# pca10156_sheet7_connectors.net
KiCad netlist of a schematic drawn in Altium Designer
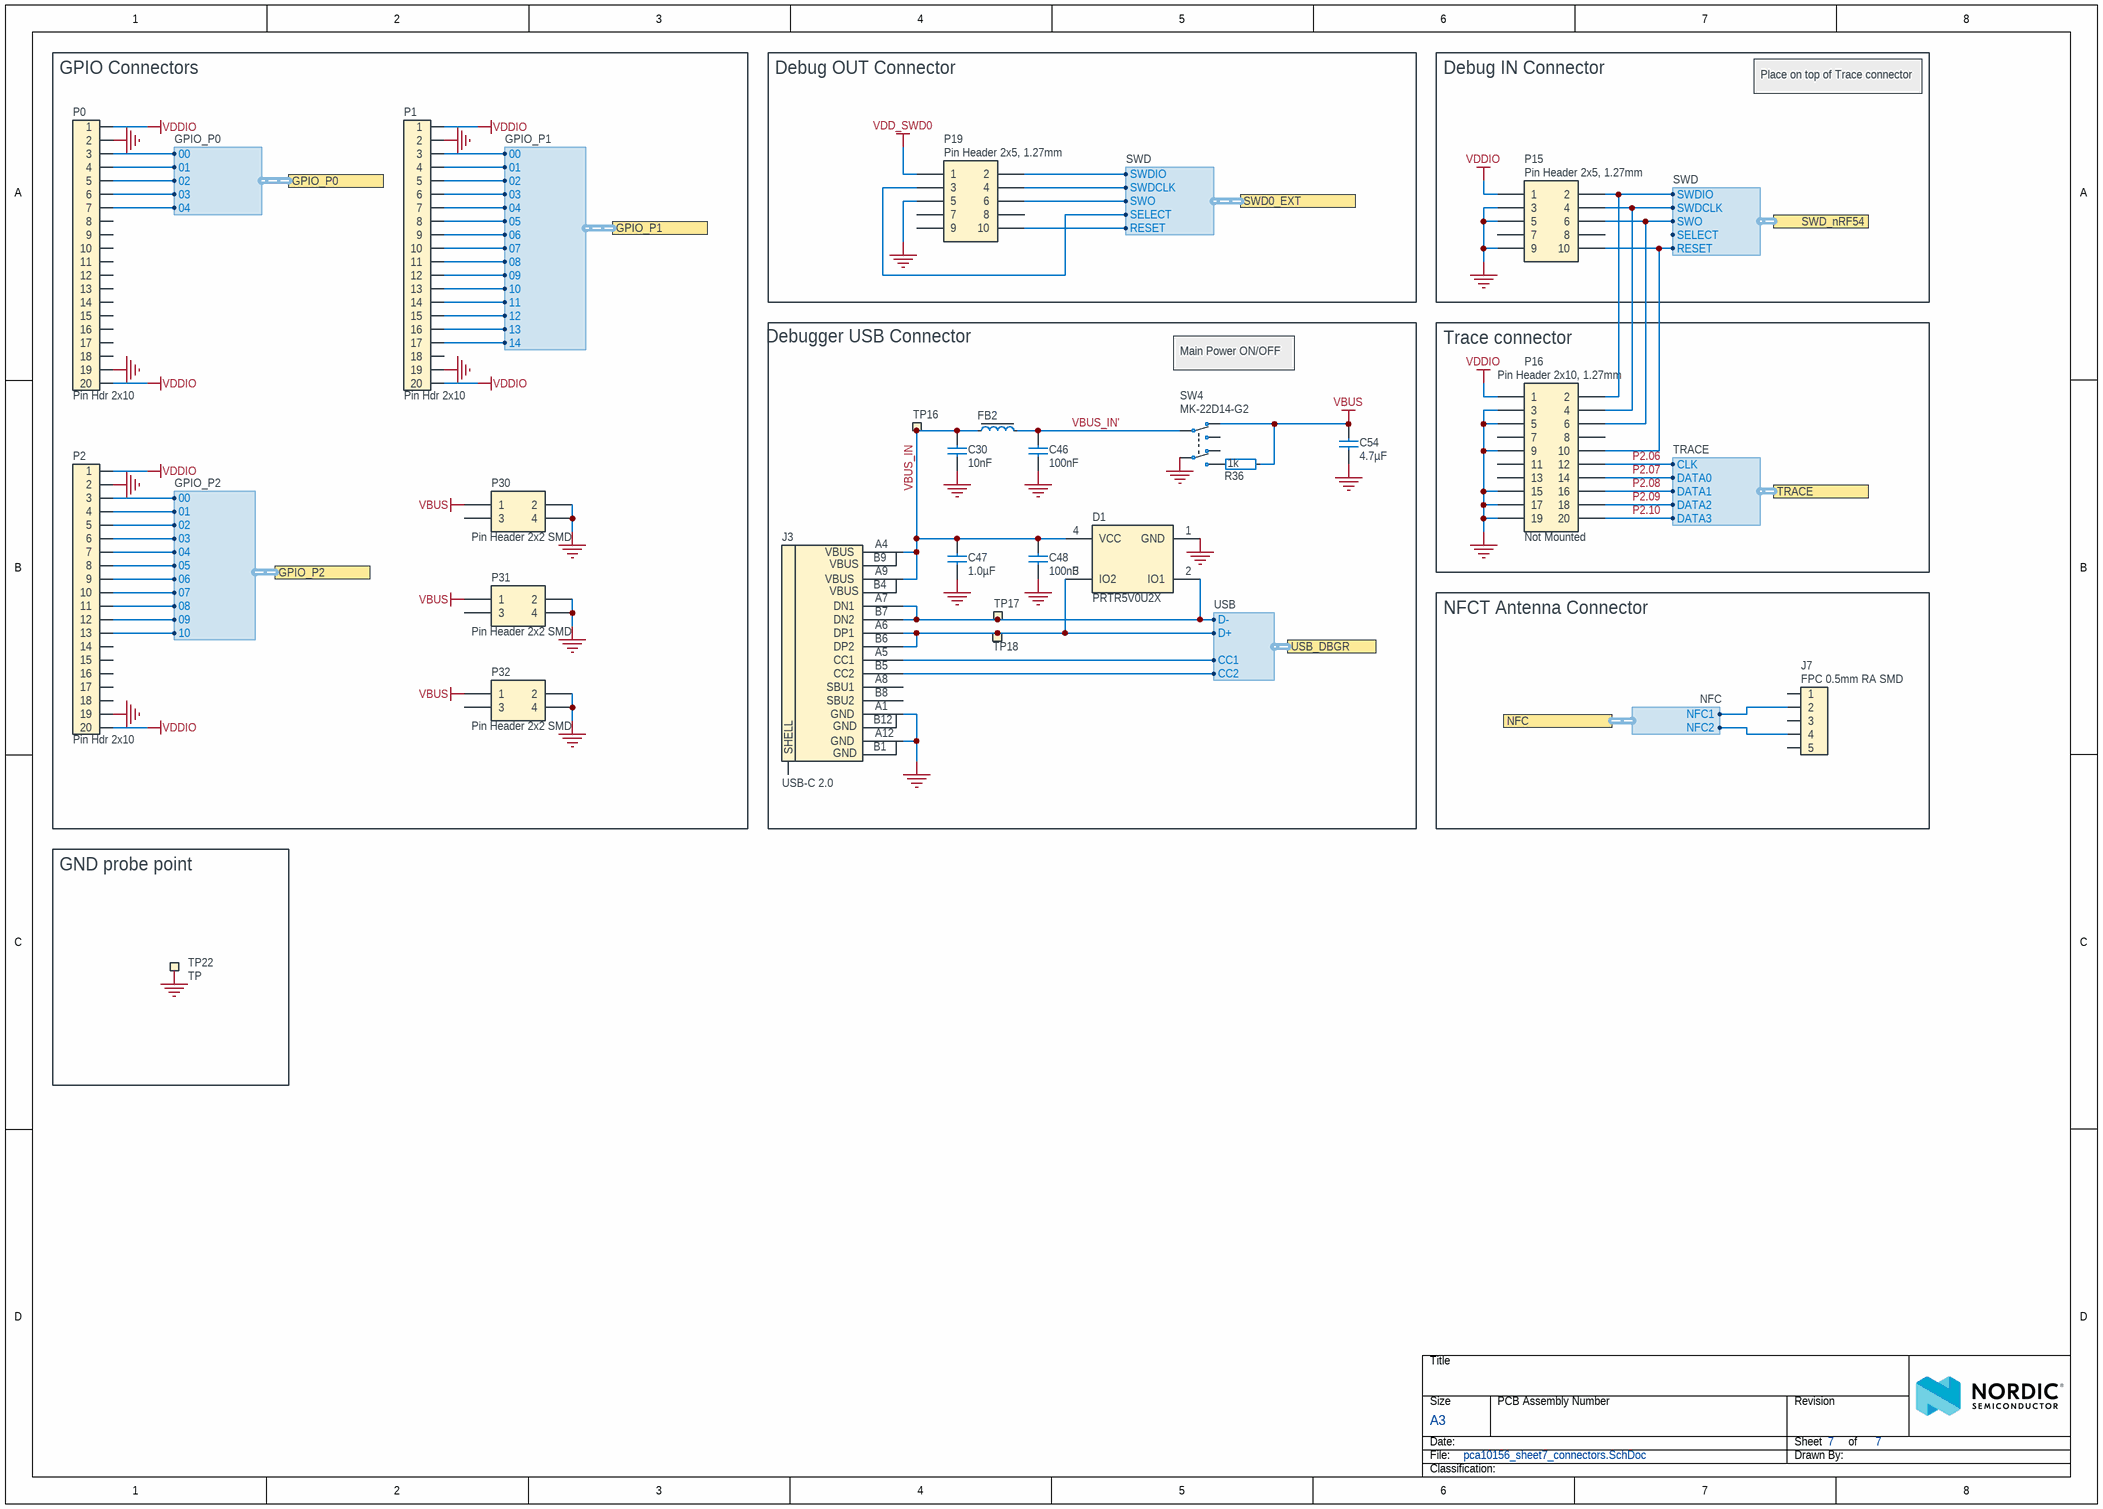
[diagram p0: pca10156_sheet7_connectors.SchDoc]

(export (version "E")
  (design (tool "Eeschema 10.0.6"))
  (components
    (comp (ref "C30")
      (value "10nF")
      (footprint "CAPC0603X03L_C")
      (description "Capacitor, X7R, ±10%")
      (fields
        (field (name "PART NUMBER") "C0201-10n")
        (field (name "MANUFACTURER") "N.A.")
        (field (name "AUTHOR") "rsk")
      )
      (libsource (lib "AltiumLib") (part "CAP"))
    )
    (comp (ref "C46")
      (value "100nF")
      (footprint "CAPC0603X03L_C")
      (description "Capacitor, X5R, ±10%")
      (fields
        (field (name "PART NUMBER") "C0201-100n")
        (field (name "MANUFACTURER") "N.A.")
        (field (name "AUTHOR") "rsk")
      )
      (libsource (lib "AltiumLib") (part "CAP"))
    )
    (comp (ref "C47")
      (value "1.0µF")
      (footprint "CAPC1005X04L")
      (description "Capacitor, Ceramic, X5R, ±10%, 16V")
      (fields
        (field (name "PART NUMBER") "C0402-1µ0-16V-X5R")
        (field (name "MANUFACTURER") "Murata")
        (field (name "AUTHOR") "rsk")
      )
      (libsource (lib "AltiumLib") (part "CAP"))
    )
    (comp (ref "C48")
      (value "100nF")
      (footprint "CAPC0603X03L_C")
      (description "Capacitor, X5R, ±10%")
      (fields
        (field (name "PART NUMBER") "C0201-100n")
        (field (name "MANUFACTURER") "N.A.")
        (field (name "AUTHOR") "rsk")
      )
      (libsource (lib "AltiumLib") (part "CAP"))
    )
    (comp (ref "C54")
      (value "4.7µF")
      (footprint "CAPC1608X06L")
      (description "Capacitor, X7S, ±10%, 10V")
      (fields
        (field (name "PART NUMBER") "C0603-4µ7-10V-X7S")
        (field (name "MANUFACTURER") "N.A.")
        (field (name "AUTHOR") "rsk")
      )
      (libsource (lib "AltiumLib") (part "CAP"))
    )
    (comp (ref "D1")
      (value "PRTR5V0U2X")
      (footprint "SOT190P230X110-4L")
      (description "Ultra low capacitance double rail-to-rail ESD protection diode")
      (fields (field (name "MANUFACTURER") "NXP Semiconductors") (field (name "AUTHOR") "rsk"))
      (libsource (lib "AltiumLib") (part "PRTR5V0U2X"))
    )
    (comp (ref "FB2")
      (value "120R/0.55A")
      (footprint "INDC1005X04L")
      (description "Ferrite Bead, 120 Ohm @ 100MHz, 500mA, 250 mOhm Max")
      (fields
        (field (name "PART NUMBER") "FB0402-120R@100M-500mA")
        (field (name "MANUFACTURER") "Murata")
        (field (name "AUTHOR") "rsk")
      )
      (libsource (lib "AltiumLib") (part "IND_F"))
    )
    (comp (ref "J3")
      (value "USB-C 2.0")
      (footprint "SD-80259-001")
      (description "USB-C Receptacle, 16 Pin, USB 2.0")
      (fields
        (field (name "PART NUMBER") "SD-80259-1021")
        (field (name "MANUFACTURER") "Bellweather Electronic Corp.")
        (field (name "AUTHOR") "getr")
      )
      (libsource (lib "AltiumLib") (part "USB4110"))
    )
    (comp (ref "J7")
      (value "FPC 0.5mm RA SMD")
      (footprint "FPC_05P-0.5mm-RA-SMD")
      (description "0.5mm FPC, 5P,Right Angle SMT,Double Contact,H=1.2mm,White, Tin plated")
      (fields
        (field (name "PART NUMBER") "FPC_05P-0.5mm-RA-SMD")
        (field (name "MANUFACTURER") "WCON")
        (field (name "AUTHOR") "rsk")
      )
      (libsource (lib "AltiumLib") (part "CONN-5"))
    )
    (comp (ref "P0")
      (value "Pin Hdr 2x10")
      (footprint "HDR_2x10-SMD")
      (description "Pin Header 2x10, 2.54mm (100mil) SMD")
      (fields
        (field (name "PART NUMBER") "Pin Header 2x10 SMD, 2.54mm")
        (field (name "MANUFACTURER") "WCON")
        (field (name "AUTHOR") "stl1")
      )
      (libsource (lib "AltiumLib") (part "CONN-20"))
    )
    (comp (ref "P1")
      (value "Pin Hdr 2x10")
      (footprint "HDR_2x10-SMD")
      (description "Pin Header 2x10, 2.54mm (100mil) SMD")
      (fields
        (field (name "PART NUMBER") "Pin Header 2x10 SMD, 2.54mm")
        (field (name "MANUFACTURER") "WCON")
        (field (name "AUTHOR") "stl1")
      )
      (libsource (lib "AltiumLib") (part "CONN-20"))
    )
    (comp (ref "P2")
      (value "Pin Hdr 2x10")
      (footprint "HDR_2x10-SMD")
      (description "Pin Header 2x10, 2.54mm (100mil) SMD")
      (fields
        (field (name "PART NUMBER") "Pin Header 2x10 SMD, 2.54mm")
        (field (name "MANUFACTURER") "WCON")
        (field (name "AUTHOR") "stl1")
      )
      (libsource (lib "AltiumLib") (part "CONN-20"))
    )
    (comp (ref "P15")
      (value "Pin Header 2x5, 1.27mm")
      (footprint "HDR_2x5-SMD-1.27mm-K")
      (description "Pin Header 2x5, 1.27mm (50mil), SMD, Keying Shroud")
      (fields
        (field (name "PART NUMBER") "Pin Header 2x5 SMD, 1.27mm, KS")
        (field (name "MANUFACTURER") "WCON")
        (field (name "AUTHOR") "rsk")
      )
      (libsource (lib "AltiumLib") (part "CONN-2x5"))
    )
    (comp (ref "P16")
      (value "Pin Header 2x10, 1.27mm")
      (footprint "HDR_2x10-SMD-1.27mm-NC")
      (description "Pin Header 2x10, 1.27mm (50mil), SMD, Keying Shroud")
      (fields
        (field (name "PART NUMBER") "Pin Header 2x10 SMD, 1.27mm, KS, N.C.")
        (field (name "MANUFACTURER") "WCON")
        (field (name "ASSEMBLY") "Not Mounted")
        (field (name "AUTHOR") "rsk")
      )
      (libsource (lib "AltiumLib") (part "CONN-2x10"))
    )
    (comp (ref "P19")
      (value "Pin Header 2x5, 1.27mm")
      (footprint "HDR_2x5-SMD-1.27mm-K")
      (description "Pin Header 2x5, 1.27mm (50mil), SMD, Keying Shroud")
      (fields
        (field (name "PART NUMBER") "Pin Header 2x5 SMD, 1.27mm, KS")
        (field (name "MANUFACTURER") "WCON")
        (field (name "AUTHOR") "rsk")
      )
      (libsource (lib "AltiumLib") (part "CONN-2x5"))
    )
    (comp (ref "P30")
      (value "Pin Header 2x2 SMD")
      (footprint "HDR_2x2-SMD")
      (description "Pin Header 2x2, SMD, 2.54mm (100mil)")
      (fields
        (field (name "MANUFACTURER") "WCON")
        (field (name "MANUFACTURER PART NUMBER") "1125-1202S0M116CR03")
        (field (name "AUTHOR") "stl1")
      )
      (libsource (lib "AltiumLib") (part "CONN-2x2"))
    )
    (comp (ref "P31")
      (value "Pin Header 2x2 SMD")
      (footprint "HDR_2x2-SMD")
      (description "Pin Header 2x2, SMD, 2.54mm (100mil)")
      (fields
        (field (name "MANUFACTURER") "WCON")
        (field (name "MANUFACTURER PART NUMBER") "1125-1202S0M116CR03")
        (field (name "AUTHOR") "stl1")
      )
      (libsource (lib "AltiumLib") (part "CONN-2x2"))
    )
    (comp (ref "P32")
      (value "Pin Header 2x2 SMD")
      (footprint "HDR_2x2-SMD")
      (description "Pin Header 2x2, SMD, 2.54mm (100mil)")
      (fields
        (field (name "MANUFACTURER") "WCON")
        (field (name "MANUFACTURER PART NUMBER") "1125-1202S0M116CR03")
        (field (name "AUTHOR") "stl1")
      )
      (libsource (lib "AltiumLib") (part "CONN-2x2"))
    )
    (comp (ref "R36")
      (value "1k")
      (footprint "RESC0603X03L_C")
      (description "Resistor, ±1%, 0.05W")
      (fields
        (field (name "PART NUMBER") "R0201-1k0")
        (field (name "MANUFACTURER") "N.A.")
        (field (name "AUTHOR") "rsk")
      )
      (libsource (lib "AltiumLib") (part "RES"))
    )
    (comp (ref "SW4")
      (value "MK-22D14-G2")
      (footprint "MK-22D14-G2")
      (description "Slide Switch DPDT")
      (fields (field (name "MANUFACTURER") "HUA-JIE CORP.") (field (name "AUTHOR") "rsk"))
      (libsource (lib "AltiumLib") (part "SW-DPDT"))
    )
    (comp (ref "TP16")
      (value "Ø1.5mm,SMD")
      (footprint "TP_SMD_D1.5mm")
      (description "1.5mm circular SMD testpad")
      (fields
        (field (name "PART NUMBER") "TP_SMD_Ø1.5MM")
        (field (name "MANUFACTURER") "Nordic Semiconductor")
        (field (name "AUTHOR") "rsk")
      )
      (libsource (lib "") (part "TESTPAD_1"))
    )
    (comp (ref "TP17")
      (value "Ø1.5mm,SMD")
      (footprint "TP_SMD_D1.5mm")
      (description "1.5mm circular SMD testpad")
      (fields
        (field (name "PART NUMBER") "TP_SMD_Ø1.5MM")
        (field (name "MANUFACTURER") "Nordic Semiconductor")
        (field (name "AUTHOR") "rsk")
      )
      (libsource (lib "") (part "TESTPAD_1"))
    )
    (comp (ref "TP18")
      (value "Ø1.5mm,SMD")
      (footprint "TP_SMD_D1.5mm")
      (description "1.5mm circular SMD testpad")
      (fields
        (field (name "PART NUMBER") "TP_SMD_Ø1.5MM")
        (field (name "MANUFACTURER") "Nordic Semiconductor")
        (field (name "AUTHOR") "rsk")
      )
      (libsource (lib "AltiumLib") (part "TESTPAD"))
    )
    (comp (ref "TP22")
      (value "TP")
      (footprint "S1751")
      (description "PC TEST POINT TIN SMD L")
      (fields
        (field (name "PART NUMBER") "TP - S1751-46R")
        (field (name "MANUFACTURER") "Harwin")
        (field (name "AUTHOR") "rsk")
      )
      (libsource (lib "AltiumLib") (part "TESTPOINT_BOM"))
    )
  )
  (nets
    (net (code "8") (name "/11") (class "Default")
      (node (ref "P1") (pin "14") (pinfunction "14_14") (pintype "passive"))
    )
    (net (code "9") (name "/12") (class "Default")
      (node (ref "P1") (pin "15") (pinfunction "15_15") (pintype "passive"))
    )
    (net (code "10") (name "/13") (class "Default")
      (node (ref "P1") (pin "16") (pinfunction "16_16") (pintype "passive"))
    )
    (net (code "11") (name "/14") (class "Default")
      (node (ref "P1") (pin "17") (pinfunction "17_17") (pintype "passive"))
    )
    (net (code "12") (name "/CC1") (class "Default")
      (node (ref "J3") (pin "A5") (pinfunction "CC1_A5") (pintype "passive"))
    )
    (net (code "13") (name "/CC2") (class "Default")
      (node (ref "J3") (pin "B5") (pinfunction "CC2_B5") (pintype "passive"))
    )
    (net (code "14") (name "/D+") (class "Default")
      (node (ref "D1") (pin "3") (pinfunction "IO2_3") (pintype "passive"))
      (node (ref "J3") (pin "A6") (pinfunction "DP1_A6") (pintype "passive"))
      (node (ref "J3") (pin "B6") (pinfunction "DP2_B6") (pintype "passive"))
      (node (ref "TP18") (pin "1") (pinfunction "1_1") (pintype "passive"))
    )
    (net (code "15") (name "/D-") (class "Default")
      (node (ref "D1") (pin "2") (pinfunction "IO1_2") (pintype "passive"))
      (node (ref "J3") (pin "A7") (pinfunction "DN1_A7") (pintype "passive"))
      (node (ref "J3") (pin "B7") (pinfunction "DN2_B7") (pintype "passive"))
      (node (ref "TP17") (pin "1") (pinfunction "1_1") (pintype "passive"))
    )
    (net (code "16") (name "/NFC1") (class "Default")
      (node (ref "J7") (pin "2") (pinfunction "2_2") (pintype "passive"))
    )
    (net (code "17") (name "/NFC2") (class "Default")
      (node (ref "J7") (pin "4") (pinfunction "4_4") (pintype "passive"))
    )
    (net (code "18") (name "/P2.06") (class "Default")
      (node (ref "P16") (pin "12") (pinfunction "12_12") (pintype "passive"))
    )
    (net (code "19") (name "/P2.07") (class "Default")
      (node (ref "P16") (pin "14") (pinfunction "14_14") (pintype "passive"))
    )
    (net (code "20") (name "/P2.08") (class "Default")
      (node (ref "P16") (pin "16") (pinfunction "16_16") (pintype "passive"))
    )
    (net (code "21") (name "/P2.09") (class "Default")
      (node (ref "P16") (pin "18") (pinfunction "18_18") (pintype "passive"))
    )
    (net (code "22") (name "/P2.10") (class "Default")
      (node (ref "P16") (pin "20") (pinfunction "20_20") (pintype "passive"))
    )
    (net (code "23") (name "/VBUS_IN") (class "Default")
      (node (ref "C30") (pin "1") (pinfunction "1_1") (pintype "passive"))
      (node (ref "C47") (pin "2") (pinfunction "2_2") (pintype "passive"))
      (node (ref "C48") (pin "2") (pinfunction "2_2") (pintype "passive"))
      (node (ref "D1") (pin "4") (pinfunction "VCC_4") (pintype "passive"))
      (node (ref "FB2") (pin "1") (pinfunction "1_1") (pintype "passive"))
      (node (ref "J3") (pin "A4") (pinfunction "VBUS_A4") (pintype "power_in"))
      (node (ref "J3") (pin "A9") (pinfunction "VBUS_A9") (pintype "power_in"))
      (node (ref "TP16") (pin "1") (pinfunction "1_1") (pintype "passive"))
    )
    (net (code "24") (name "/VBUS_IN'") (class "Default")
      (node (ref "C46") (pin "2") (pinfunction "2_2") (pintype "passive"))
      (node (ref "FB2") (pin "2") (pinfunction "2_2") (pintype "passive"))
      (node (ref "SW4") (pin "2") (pinfunction "COM-1_2") (pintype "passive"))
    )
    (net (code "32") (name "GND") (class "Default")
      (node (ref "C30") (pin "2") (pinfunction "2_2") (pintype "passive"))
      (node (ref "C46") (pin "1") (pinfunction "1_1") (pintype "passive"))
      (node (ref "C47") (pin "1") (pinfunction "1_1") (pintype "passive"))
      (node (ref "C48") (pin "1") (pinfunction "1_1") (pintype "passive"))
      (node (ref "C54") (pin "2") (pinfunction "2_2") (pintype "passive"))
      (node (ref "D1") (pin "1") (pinfunction "GND_1") (pintype "passive"))
      (node (ref "J3") (pin "A1") (pinfunction "GND_A1") (pintype "power_in"))
      (node (ref "J3") (pin "A12") (pinfunction "GND_A12") (pintype "power_in"))
      (node (ref "P0") (pin "19") (pinfunction "19_19") (pintype "passive"))
      (node (ref "P0") (pin "2") (pinfunction "2_2") (pintype "passive"))
      (node (ref "P1") (pin "19") (pinfunction "19_19") (pintype "passive"))
      (node (ref "P1") (pin "2") (pinfunction "2_2") (pintype "passive"))
      (node (ref "P15") (pin "3") (pinfunction "3_3") (pintype "passive"))
      (node (ref "P15") (pin "5") (pinfunction "5_5") (pintype "passive"))
      (node (ref "P15") (pin "9") (pinfunction "9_9") (pintype "passive"))
      (node (ref "P16") (pin "15") (pinfunction "15_15") (pintype "passive"))
      (node (ref "P16") (pin "17") (pinfunction "17_17") (pintype "passive"))
      (node (ref "P16") (pin "19") (pinfunction "19_19") (pintype "passive"))
      (node (ref "P16") (pin "3") (pinfunction "3_3") (pintype "passive"))
      (node (ref "P16") (pin "5") (pinfunction "5_5") (pintype "passive"))
      (node (ref "P16") (pin "9") (pinfunction "9_9") (pintype "passive"))
      (node (ref "P19") (pin "5") (pinfunction "5_5") (pintype "passive"))
      (node (ref "P2") (pin "19") (pinfunction "19_19") (pintype "passive"))
      (node (ref "P2") (pin "2") (pinfunction "2_2") (pintype "passive"))
      (node (ref "P30") (pin "2") (pinfunction "2_2") (pintype "passive"))
      (node (ref "P30") (pin "4") (pinfunction "4_4") (pintype "passive"))
      (node (ref "P31") (pin "2") (pinfunction "2_2") (pintype "passive"))
      (node (ref "P31") (pin "4") (pinfunction "4_4") (pintype "passive"))
      (node (ref "P32") (pin "2") (pinfunction "2_2") (pintype "passive"))
      (node (ref "P32") (pin "4") (pinfunction "4_4") (pintype "passive"))
      (node (ref "SW4") (pin "5") (pinfunction "COM-2_5") (pintype "passive"))
      (node (ref "TP22") (pin "1") (pinfunction "1_1") (pintype "passive"))
    )
    (net (code "33") (name "Net-(P15-Pad2)") (class "Default")
      (node (ref "P15") (pin "2") (pinfunction "2_2") (pintype "passive"))
      (node (ref "P16") (pin "2") (pinfunction "2_2") (pintype "passive"))
    )
    (net (code "34") (name "Net-(P15-Pad4)") (class "Default")
      (node (ref "P15") (pin "4") (pinfunction "4_4") (pintype "passive"))
      (node (ref "P16") (pin "4") (pinfunction "4_4") (pintype "passive"))
    )
    (net (code "35") (name "Net-(P15-Pad6)") (class "Default")
      (node (ref "P15") (pin "6") (pinfunction "6_6") (pintype "passive"))
      (node (ref "P16") (pin "6") (pinfunction "6_6") (pintype "passive"))
    )
    (net (code "36") (name "Net-(P15-Pad10)") (class "Default")
      (node (ref "P15") (pin "10") (pinfunction "10_10") (pintype "passive"))
      (node (ref "P16") (pin "10") (pinfunction "10_10") (pintype "passive"))
    )
    (net (code "37") (name "Net-(SW4-N.O-2)") (class "Default")
      (node (ref "R36") (pin "1") (pinfunction "1_1") (pintype "passive"))
      (node (ref "SW4") (pin "4") (pinfunction "N.O-2_4") (pintype "passive"))
    )
    (net (code "38") (name "VBUS") (class "Default")
      (node (ref "C54") (pin "1") (pinfunction "1_1") (pintype "passive"))
      (node (ref "P30") (pin "1") (pinfunction "1_1") (pintype "passive"))
      (node (ref "P31") (pin "1") (pinfunction "1_1") (pintype "passive"))
      (node (ref "P32") (pin "1") (pinfunction "1_1") (pintype "passive"))
      (node (ref "R36") (pin "2") (pinfunction "2_2") (pintype "passive"))
      (node (ref "SW4") (pin "3") (pinfunction "N.C-1_3") (pintype "passive"))
    )
    (net (code "39") (name "VDDIO") (class "Default")
      (node (ref "P0") (pin "1") (pinfunction "1_1") (pintype "passive"))
      (node (ref "P0") (pin "20") (pinfunction "20_20") (pintype "passive"))
      (node (ref "P1") (pin "1") (pinfunction "1_1") (pintype "passive"))
      (node (ref "P1") (pin "20") (pinfunction "20_20") (pintype "passive"))
      (node (ref "P15") (pin "1") (pinfunction "1_1") (pintype "passive"))
      (node (ref "P16") (pin "1") (pinfunction "1_1") (pintype "passive"))
      (node (ref "P2") (pin "1") (pinfunction "1_1") (pintype "passive"))
      (node (ref "P2") (pin "20") (pinfunction "20_20") (pintype "passive"))
    )
    (net (code "40") (name "VDD_SWD0") (class "Default")
      (node (ref "P19") (pin "1") (pinfunction "1_1") (pintype "passive"))
    )
    (net (code "41") (name "unconnected-(J3-SBU1-PadA8)") (class "Default")
      (node (ref "J3") (pin "A8") (pinfunction "SBU1_A8") (pintype "passive"))
    )
    (net (code "42") (name "unconnected-(J3-SBU2-PadB8)") (class "Default")
      (node (ref "J3") (pin "B8") (pinfunction "SBU2_B8") (pintype "passive"))
    )
    (net (code "43") (name "unconnected-(J3-SHELL-PadSHLD)") (class "Default")
      (node (ref "J3") (pin "SHLD") (pinfunction "SHELL_SHLD") (pintype "power_in"))
    )
    (net (code "44") (name "unconnected-(J7-Pad1)") (class "Default")
      (node (ref "J7") (pin "1") (pinfunction "1_1") (pintype "passive"))
    )
    (net (code "45") (name "unconnected-(J7-Pad3)") (class "Default")
      (node (ref "J7") (pin "3") (pinfunction "3_3") (pintype "passive"))
    )
    (net (code "46") (name "unconnected-(J7-Pad5)") (class "Default")
      (node (ref "J7") (pin "5") (pinfunction "5_5") (pintype "passive"))
    )
    (net (code "47") (name "unconnected-(P0-Pad3)") (class "Default")
      (node (ref "P0") (pin "3") (pinfunction "3_3") (pintype "passive"))
    )
    (net (code "48") (name "unconnected-(P0-Pad4)") (class "Default")
      (node (ref "P0") (pin "4") (pinfunction "4_4") (pintype "passive"))
    )
    (net (code "49") (name "unconnected-(P0-Pad5)") (class "Default")
      (node (ref "P0") (pin "5") (pinfunction "5_5") (pintype "passive"))
    )
    (net (code "50") (name "unconnected-(P0-Pad6)") (class "Default")
      (node (ref "P0") (pin "6") (pinfunction "6_6") (pintype "passive"))
    )
    (net (code "51") (name "unconnected-(P0-Pad7)") (class "Default")
      (node (ref "P0") (pin "7") (pinfunction "7_7") (pintype "passive"))
    )
    (net (code "52") (name "unconnected-(P0-Pad8)") (class "Default")
      (node (ref "P0") (pin "8") (pinfunction "8_8") (pintype "passive"))
    )
    (net (code "53") (name "unconnected-(P0-Pad9)") (class "Default")
      (node (ref "P0") (pin "9") (pinfunction "9_9") (pintype "passive"))
    )
    (net (code "54") (name "unconnected-(P0-Pad10)") (class "Default")
      (node (ref "P0") (pin "10") (pinfunction "10_10") (pintype "passive"))
    )
    (net (code "55") (name "unconnected-(P0-Pad11)") (class "Default")
      (node (ref "P0") (pin "11") (pinfunction "11_11") (pintype "passive"))
    )
    (net (code "56") (name "unconnected-(P0-Pad12)") (class "Default")
      (node (ref "P0") (pin "12") (pinfunction "12_12") (pintype "passive"))
    )
    (net (code "57") (name "unconnected-(P0-Pad13)") (class "Default")
      (node (ref "P0") (pin "13") (pinfunction "13_13") (pintype "passive"))
    )
    (net (code "58") (name "unconnected-(P0-Pad14)") (class "Default")
      (node (ref "P0") (pin "14") (pinfunction "14_14") (pintype "passive"))
    )
    (net (code "59") (name "unconnected-(P0-Pad15)") (class "Default")
      (node (ref "P0") (pin "15") (pinfunction "15_15") (pintype "passive"))
    )
    (net (code "60") (name "unconnected-(P0-Pad16)") (class "Default")
      (node (ref "P0") (pin "16") (pinfunction "16_16") (pintype "passive"))
    )
    (net (code "61") (name "unconnected-(P0-Pad17)") (class "Default")
      (node (ref "P0") (pin "17") (pinfunction "17_17") (pintype "passive"))
    )
    (net (code "62") (name "unconnected-(P0-Pad18)") (class "Default")
      (node (ref "P0") (pin "18") (pinfunction "18_18") (pintype "passive"))
    )
    (net (code "63") (name "unconnected-(P1-Pad3)") (class "Default")
      (node (ref "P1") (pin "3") (pinfunction "3_3") (pintype "passive"))
    )
    (net (code "64") (name "unconnected-(P1-Pad4)") (class "Default")
      (node (ref "P1") (pin "4") (pinfunction "4_4") (pintype "passive"))
    )
    (net (code "65") (name "unconnected-(P1-Pad5)") (class "Default")
      (node (ref "P1") (pin "5") (pinfunction "5_5") (pintype "passive"))
    )
    (net (code "66") (name "unconnected-(P1-Pad6)") (class "Default")
      (node (ref "P1") (pin "6") (pinfunction "6_6") (pintype "passive"))
    )
    (net (code "67") (name "unconnected-(P1-Pad7)") (class "Default")
      (node (ref "P1") (pin "7") (pinfunction "7_7") (pintype "passive"))
    )
    (net (code "68") (name "unconnected-(P1-Pad8)") (class "Default")
      (node (ref "P1") (pin "8") (pinfunction "8_8") (pintype "passive"))
    )
    (net (code "69") (name "unconnected-(P1-Pad9)") (class "Default")
      (node (ref "P1") (pin "9") (pinfunction "9_9") (pintype "passive"))
    )
    (net (code "70") (name "unconnected-(P1-Pad10)") (class "Default")
      (node (ref "P1") (pin "10") (pinfunction "10_10") (pintype "passive"))
    )
    (net (code "71") (name "unconnected-(P1-Pad11)") (class "Default")
      (node (ref "P1") (pin "11") (pinfunction "11_11") (pintype "passive"))
    )
    (net (code "72") (name "unconnected-(P1-Pad12)") (class "Default")
      (node (ref "P1") (pin "12") (pinfunction "12_12") (pintype "passive"))
    )
    (net (code "73") (name "unconnected-(P1-Pad13)") (class "Default")
      (node (ref "P1") (pin "13") (pinfunction "13_13") (pintype "passive"))
    )
    (net (code "74") (name "unconnected-(P1-Pad18)") (class "Default")
      (node (ref "P1") (pin "18") (pinfunction "18_18") (pintype "passive"))
    )
    (net (code "75") (name "unconnected-(P2-Pad3)") (class "Default")
      (node (ref "P2") (pin "3") (pinfunction "3_3") (pintype "passive"))
    )
    (net (code "76") (name "unconnected-(P2-Pad4)") (class "Default")
      (node (ref "P2") (pin "4") (pinfunction "4_4") (pintype "passive"))
    )
    (net (code "77") (name "unconnected-(P2-Pad5)") (class "Default")
      (node (ref "P2") (pin "5") (pinfunction "5_5") (pintype "passive"))
    )
    (net (code "78") (name "unconnected-(P2-Pad6)") (class "Default")
      (node (ref "P2") (pin "6") (pinfunction "6_6") (pintype "passive"))
    )
    (net (code "79") (name "unconnected-(P2-Pad7)") (class "Default")
      (node (ref "P2") (pin "7") (pinfunction "7_7") (pintype "passive"))
    )
    (net (code "80") (name "unconnected-(P2-Pad8)") (class "Default")
      (node (ref "P2") (pin "8") (pinfunction "8_8") (pintype "passive"))
    )
    (net (code "81") (name "unconnected-(P2-Pad9)") (class "Default")
      (node (ref "P2") (pin "9") (pinfunction "9_9") (pintype "passive"))
    )
    (net (code "82") (name "unconnected-(P2-Pad10)") (class "Default")
      (node (ref "P2") (pin "10") (pinfunction "10_10") (pintype "passive"))
    )
    (net (code "83") (name "unconnected-(P2-Pad11)") (class "Default")
      (node (ref "P2") (pin "11") (pinfunction "11_11") (pintype "passive"))
    )
    (net (code "84") (name "unconnected-(P2-Pad12)") (class "Default")
      (node (ref "P2") (pin "12") (pinfunction "12_12") (pintype "passive"))
    )
    (net (code "85") (name "unconnected-(P2-Pad13)") (class "Default")
      (node (ref "P2") (pin "13") (pinfunction "13_13") (pintype "passive"))
    )
    (net (code "86") (name "unconnected-(P2-Pad14)") (class "Default")
      (node (ref "P2") (pin "14") (pinfunction "14_14") (pintype "passive"))
    )
    (net (code "87") (name "unconnected-(P2-Pad15)") (class "Default")
      (node (ref "P2") (pin "15") (pinfunction "15_15") (pintype "passive"))
    )
    (net (code "88") (name "unconnected-(P2-Pad16)") (class "Default")
      (node (ref "P2") (pin "16") (pinfunction "16_16") (pintype "passive"))
    )
    (net (code "89") (name "unconnected-(P2-Pad17)") (class "Default")
      (node (ref "P2") (pin "17") (pinfunction "17_17") (pintype "passive"))
    )
    (net (code "90") (name "unconnected-(P2-Pad18)") (class "Default")
      (node (ref "P2") (pin "18") (pinfunction "18_18") (pintype "passive"))
    )
    (net (code "91") (name "unconnected-(P15-Pad7)") (class "Default")
      (node (ref "P15") (pin "7") (pinfunction "7_7") (pintype "passive"))
    )
    (net (code "92") (name "unconnected-(P15-Pad8)") (class "Default")
      (node (ref "P15") (pin "8") (pinfunction "8_8") (pintype "passive"))
    )
    (net (code "93") (name "unconnected-(P16-Pad7)") (class "Default")
      (node (ref "P16") (pin "7") (pinfunction "7_7") (pintype "passive"))
    )
    (net (code "94") (name "unconnected-(P16-Pad8)") (class "Default")
      (node (ref "P16") (pin "8") (pinfunction "8_8") (pintype "passive"))
    )
    (net (code "95") (name "unconnected-(P16-Pad11)") (class "Default")
      (node (ref "P16") (pin "11") (pinfunction "11_11") (pintype "passive"))
    )
    (net (code "96") (name "unconnected-(P16-Pad13)") (class "Default")
      (node (ref "P16") (pin "13") (pinfunction "13_13") (pintype "passive"))
    )
    (net (code "97") (name "unconnected-(P19-Pad2)") (class "Default")
      (node (ref "P19") (pin "2") (pinfunction "2_2") (pintype "passive"))
    )
    (net (code "98") (name "unconnected-(P19-Pad3)") (class "Default")
      (node (ref "P19") (pin "3") (pinfunction "3_3") (pintype "passive"))
    )
    (net (code "99") (name "unconnected-(P19-Pad4)") (class "Default")
      (node (ref "P19") (pin "4") (pinfunction "4_4") (pintype "passive"))
    )
    (net (code "100") (name "unconnected-(P19-Pad6)") (class "Default")
      (node (ref "P19") (pin "6") (pinfunction "6_6") (pintype "passive"))
    )
    (net (code "101") (name "unconnected-(P19-Pad7)") (class "Default")
      (node (ref "P19") (pin "7") (pinfunction "7_7") (pintype "passive"))
    )
    (net (code "102") (name "unconnected-(P19-Pad8)") (class "Default")
      (node (ref "P19") (pin "8") (pinfunction "8_8") (pintype "passive"))
    )
    (net (code "103") (name "unconnected-(P19-Pad9)") (class "Default")
      (node (ref "P19") (pin "9") (pinfunction "9_9") (pintype "passive"))
    )
    (net (code "104") (name "unconnected-(P19-Pad10)") (class "Default")
      (node (ref "P19") (pin "10") (pinfunction "10_10") (pintype "passive"))
    )
    (net (code "105") (name "unconnected-(P30-Pad3)") (class "Default")
      (node (ref "P30") (pin "3") (pinfunction "3_3") (pintype "passive"))
    )
    (net (code "106") (name "unconnected-(P31-Pad3)") (class "Default")
      (node (ref "P31") (pin "3") (pinfunction "3_3") (pintype "passive"))
    )
    (net (code "107") (name "unconnected-(P32-Pad3)") (class "Default")
      (node (ref "P32") (pin "3") (pinfunction "3_3") (pintype "passive"))
    )
    (net (code "108") (name "unconnected-(SW4-N.C-2-Pad6)") (class "Default")
      (node (ref "SW4") (pin "6") (pinfunction "N.C-2_6") (pintype "passive"))
    )
    (net (code "109") (name "unconnected-(SW4-N.O-1-Pad1)") (class "Default")
      (node (ref "SW4") (pin "1") (pinfunction "N.O-1_1") (pintype "passive"))
    )
  )
)
